# MultiDrop.net
KiCad netlist of a schematic drawn in EAGLE
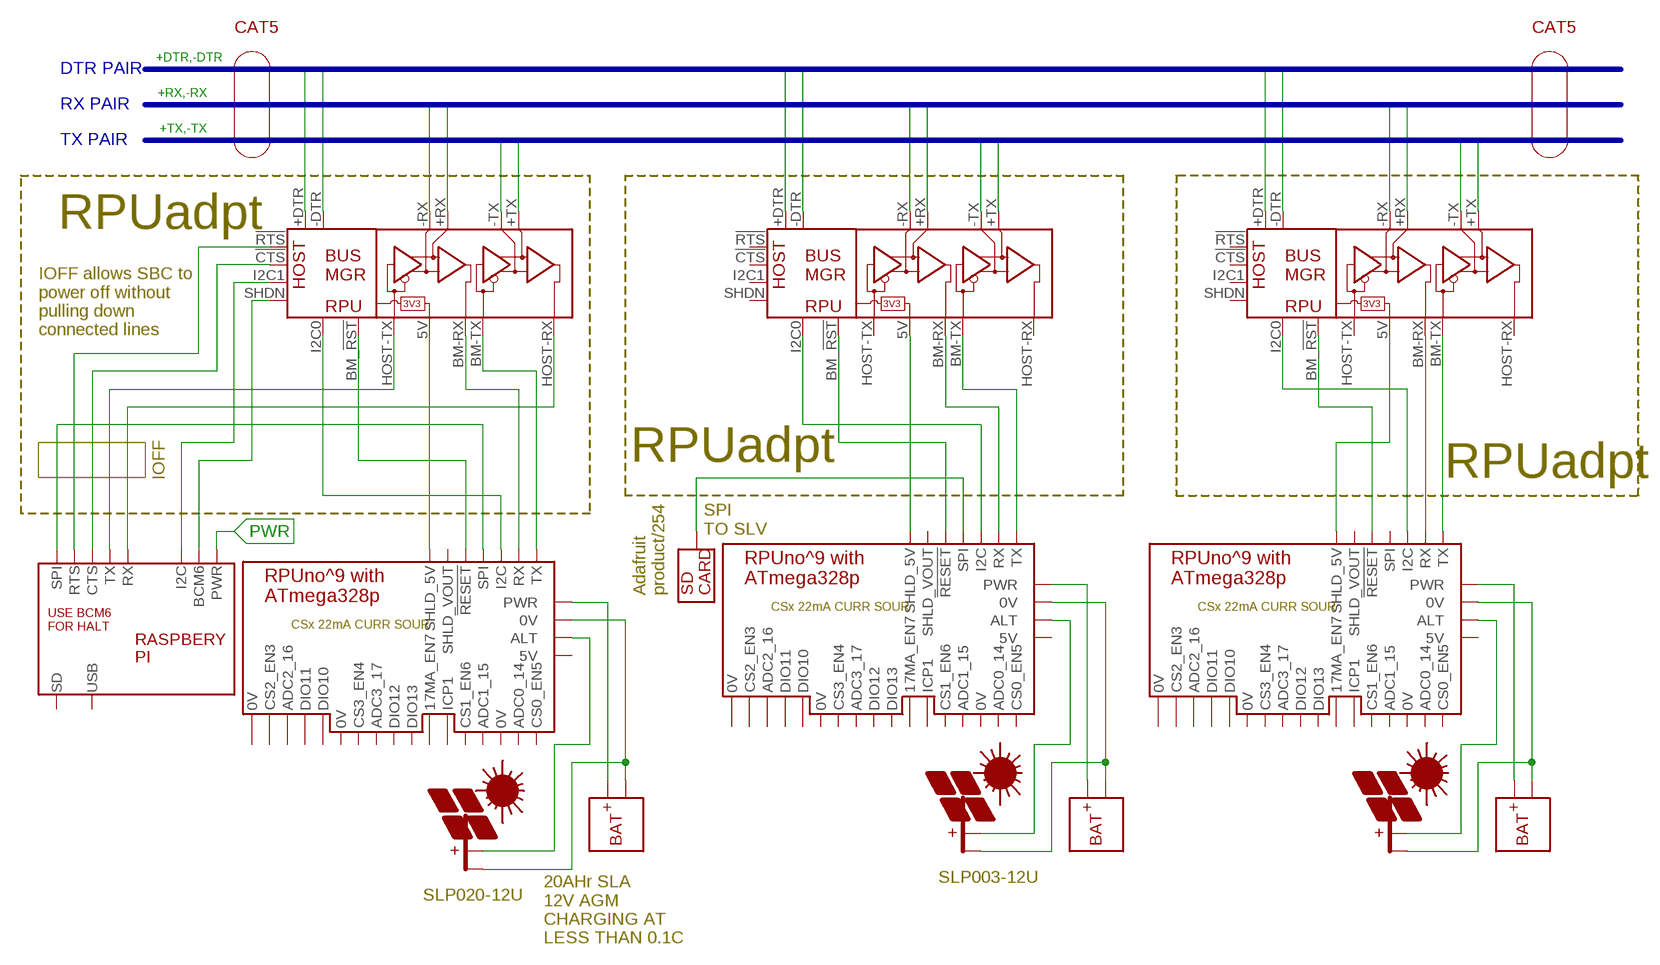
[diagram p0: schematic, sheet 1]

(export (version "E")
  (design (tool "Eeschema 10.0.6"))
  (components
    (comp (ref "BM1")
      (value "RPUNO")
      (footprint "eagle-import:NA-30")
      (libsource (lib "eagle-import") (part "RPUNO"))
    )
    (comp (ref "BM2")
      (value "RPUNO")
      (footprint "eagle-import:NA-30")
      (libsource (lib "eagle-import") (part "RPUNO"))
    )
    (comp (ref "BM3")
      (value "RPUNO")
      (footprint "eagle-import:NA-30")
      (libsource (lib "eagle-import") (part "RPUNO"))
    )
    (comp (ref "PV1")
      (value "PV")
      (footprint "eagle-import:NA-30")
      (libsource (lib "eagle-import") (part "PV"))
    )
    (comp (ref "PV2")
      (value "PV")
      (footprint "eagle-import:NA-30")
      (libsource (lib "eagle-import") (part "PV"))
    )
    (comp (ref "PV3")
      (value "PV")
      (footprint "eagle-import:NA-30")
      (libsource (lib "eagle-import") (part "PV"))
    )
    (comp (ref "SD1")
      (value "SD")
      (footprint "eagle-import:NA-30")
      (libsource (lib "eagle-import") (part "SD"))
    )
    (comp (ref "U$1")
      (value "BUS_MGR")
      (footprint "eagle-import:WITH_RPU_NAMES")
      (libsource (lib "eagle-import") (part "BUS_MGR"))
    )
    (comp (ref "U$2")
      (value "BUS_MGR")
      (footprint "eagle-import:WITH_RPU_NAMES")
      (libsource (lib "eagle-import") (part "BUS_MGR"))
    )
    (comp (ref "U$3")
      (value "BAT")
      (footprint "eagle-import:NA-30")
      (libsource (lib "eagle-import") (part "BAT"))
    )
    (comp (ref "U$4")
      (value "BUS_MGR")
      (footprint "eagle-import:WITH_RPU_NAMES")
      (libsource (lib "eagle-import") (part "BUS_MGR"))
    )
    (comp (ref "U$5")
      (value "BAT")
      (footprint "eagle-import:NA-30")
      (libsource (lib "eagle-import") (part "BAT"))
    )
    (comp (ref "U$7")
      (value "PI")
      (footprint "eagle-import:NA-30")
      (libsource (lib "eagle-import") (part "PI"))
    )
    (comp (ref "U$9")
      (value "BAT")
      (footprint "eagle-import:NA-30")
      (libsource (lib "eagle-import") (part "BAT"))
    )
  )
  (nets
    (net (code "10") (name "Net-(BM1-ALT)") (class "Default")
      (node (ref "BM1") (pin "20") (pinfunction "ALT_20") (pintype "bidirectional"))
      (node (ref "PV1") (pin "1") (pinfunction "+PV_1") (pintype "bidirectional"))
    )
    (net (code "11") (name "Net-(BM1-I2C)") (class "Default")
      (node (ref "BM1") (pin "3") (pinfunction "I2C_3") (pintype "bidirectional"))
      (node (ref "U$2") (pin "I2C0") (pinfunction "I2C0_I2C0") (pintype "bidirectional"))
    )
    (net (code "12") (name "Net-(BM1-PWR)") (class "Default")
      (node (ref "BM1") (pin "8") (pinfunction "PWR_8") (pintype "bidirectional"))
      (node (ref "U$3") (pin "1") (pinfunction "+BAT_1") (pintype "bidirectional"))
    )
    (net (code "13") (name "Net-(BM1-RX)") (class "Default")
      (node (ref "BM1") (pin "2") (pinfunction "RX_2") (pintype "bidirectional"))
      (node (ref "U$2") (pin "BM-RX") (pinfunction "BM_RX_BM-RX") (pintype "bidirectional"))
    )
    (net (code "14") (name "Net-(BM1-SHLD_5V)") (class "Default")
      (node (ref "BM1") (pin "6") (pinfunction "SHLD_5V_6") (pintype "bidirectional"))
      (node (ref "U$2") (pin "5V") (pinfunction "PWR_5V") (pintype "bidirectional"))
    )
    (net (code "15") (name "Net-(BM1-SPI)") (class "Default")
      (node (ref "BM1") (pin "4") (pinfunction "SPI_4") (pintype "bidirectional"))
      (node (ref "SD1") (pin "1") (pinfunction "PV_PWR_1") (pintype "bidirectional"))
    )
    (net (code "16") (name "Net-(BM1-TX)") (class "Default")
      (node (ref "BM1") (pin "1") (pinfunction "TX_1") (pintype "bidirectional"))
      (node (ref "U$2") (pin "BM-TX") (pinfunction "BM_TX_BM-TX") (pintype "bidirectional"))
    )
    (net (code "17") (name "Net-(BM1-~{RESET})") (class "Default")
      (node (ref "BM1") (pin "5") (pinfunction "~{RESET}_5") (pintype "bidirectional"))
      (node (ref "U$2") (pin "BM_!RST!") (pinfunction "BM-~{RST}_BM_!RST!") (pintype "bidirectional"))
    )
    (net (code "18") (name "Net-(BM2-ALT)") (class "Default")
      (node (ref "BM2") (pin "20") (pinfunction "ALT_20") (pintype "bidirectional"))
      (node (ref "PV2") (pin "1") (pinfunction "+PV_1") (pintype "bidirectional"))
    )
    (net (code "19") (name "Net-(BM2-I2C)") (class "Default")
      (node (ref "BM2") (pin "3") (pinfunction "I2C_3") (pintype "bidirectional"))
      (node (ref "U$1") (pin "I2C0") (pinfunction "I2C0_I2C0") (pintype "bidirectional"))
    )
    (net (code "20") (name "Net-(BM2-PWR)") (class "Default")
      (node (ref "BM2") (pin "8") (pinfunction "PWR_8") (pintype "bidirectional"))
      (node (ref "U$9") (pin "1") (pinfunction "+BAT_1") (pintype "bidirectional"))
    )
    (net (code "21") (name "Net-(BM2-RX)") (class "Default")
      (node (ref "BM2") (pin "2") (pinfunction "RX_2") (pintype "bidirectional"))
      (node (ref "U$1") (pin "BM-RX") (pinfunction "BM_RX_BM-RX") (pintype "bidirectional"))
    )
    (net (code "22") (name "Net-(BM2-SHLD_5V)") (class "Default")
      (node (ref "BM2") (pin "6") (pinfunction "SHLD_5V_6") (pintype "bidirectional"))
      (node (ref "U$1") (pin "5V") (pinfunction "PWR_5V") (pintype "bidirectional"))
    )
    (net (code "23") (name "Net-(BM2-SPI)") (class "Default")
      (node (ref "BM2") (pin "4") (pinfunction "SPI_4") (pintype "bidirectional"))
      (node (ref "U$7") (pin "10") (pinfunction "SPI_10") (pintype "bidirectional"))
    )
    (net (code "24") (name "Net-(BM2-TX)") (class "Default")
      (node (ref "BM2") (pin "1") (pinfunction "TX_1") (pintype "bidirectional"))
      (node (ref "U$1") (pin "BM-TX") (pinfunction "BM_TX_BM-TX") (pintype "bidirectional"))
    )
    (net (code "25") (name "Net-(BM2-~{RESET})") (class "Default")
      (node (ref "BM2") (pin "5") (pinfunction "~{RESET}_5") (pintype "bidirectional"))
      (node (ref "U$1") (pin "BM_!RST!") (pinfunction "BM-~{RST}_BM_!RST!") (pintype "bidirectional"))
    )
    (net (code "26") (name "Net-(BM3-ALT)") (class "Default")
      (node (ref "BM3") (pin "20") (pinfunction "ALT_20") (pintype "bidirectional"))
      (node (ref "PV3") (pin "1") (pinfunction "+PV_1") (pintype "bidirectional"))
    )
    (net (code "27") (name "Net-(BM3-I2C)") (class "Default")
      (node (ref "BM3") (pin "3") (pinfunction "I2C_3") (pintype "bidirectional"))
      (node (ref "U$4") (pin "I2C0") (pinfunction "I2C0_I2C0") (pintype "bidirectional"))
    )
    (net (code "28") (name "Net-(BM3-PWR)") (class "Default")
      (node (ref "BM3") (pin "8") (pinfunction "PWR_8") (pintype "bidirectional"))
      (node (ref "U$5") (pin "1") (pinfunction "+BAT_1") (pintype "bidirectional"))
    )
    (net (code "29") (name "Net-(BM3-RX)") (class "Default")
      (node (ref "BM3") (pin "2") (pinfunction "RX_2") (pintype "bidirectional"))
      (node (ref "U$4") (pin "BM-RX") (pinfunction "BM_RX_BM-RX") (pintype "bidirectional"))
    )
    (net (code "30") (name "Net-(BM3-SHLD_5V)") (class "Default")
      (node (ref "BM3") (pin "6") (pinfunction "SHLD_5V_6") (pintype "bidirectional"))
      (node (ref "U$4") (pin "5V") (pinfunction "PWR_5V") (pintype "bidirectional"))
    )
    (net (code "31") (name "Net-(BM3-TX)") (class "Default")
      (node (ref "BM3") (pin "1") (pinfunction "TX_1") (pintype "bidirectional"))
      (node (ref "U$4") (pin "BM-TX") (pinfunction "BM_TX_BM-TX") (pintype "bidirectional"))
    )
    (net (code "32") (name "Net-(BM3-~{RESET})") (class "Default")
      (node (ref "BM3") (pin "5") (pinfunction "~{RESET}_5") (pintype "bidirectional"))
      (node (ref "U$4") (pin "BM_!RST!") (pinfunction "BM-~{RST}_BM_!RST!") (pintype "bidirectional"))
    )
    (net (code "33") (name "Net-(PV1--PV)") (class "Default")
      (node (ref "BM1") (pin "9") (pinfunction "0V_9") (pintype "bidirectional"))
      (node (ref "PV1") (pin "2") (pinfunction "-PV_2") (pintype "bidirectional"))
      (node (ref "U$3") (pin "2") (pinfunction "-BAT_2") (pintype "bidirectional"))
    )
    (net (code "34") (name "Net-(PV2--PV)") (class "Default")
      (node (ref "BM2") (pin "9") (pinfunction "0V_9") (pintype "bidirectional"))
      (node (ref "PV2") (pin "2") (pinfunction "-PV_2") (pintype "bidirectional"))
      (node (ref "U$9") (pin "2") (pinfunction "-BAT_2") (pintype "bidirectional"))
    )
    (net (code "35") (name "Net-(PV3--PV)") (class "Default")
      (node (ref "BM3") (pin "9") (pinfunction "0V_9") (pintype "bidirectional"))
      (node (ref "PV3") (pin "2") (pinfunction "-PV_2") (pintype "bidirectional"))
      (node (ref "U$5") (pin "2") (pinfunction "-BAT_2") (pintype "bidirectional"))
    )
    (net (code "36") (name "Net-(U$1-HOST_RX)") (class "Default")
      (node (ref "U$1") (pin "HOST-RX") (pinfunction "HOST_RX_HOST-RX") (pintype "bidirectional"))
      (node (ref "U$7") (pin "3") (pinfunction "RX_3") (pintype "bidirectional"))
    )
    (net (code "37") (name "Net-(U$1-HOST_TX)") (class "Default")
      (node (ref "U$1") (pin "HOST-TX") (pinfunction "HOST_TX_HOST-TX") (pintype "bidirectional"))
      (node (ref "U$7") (pin "4") (pinfunction "TX_4") (pintype "bidirectional"))
    )
    (net (code "38") (name "Net-(U$1-~{CTS})") (class "Default")
      (node (ref "U$1") (pin "!CTS") (pinfunction "~{CTS}_!CTS") (pintype "bidirectional"))
      (node (ref "U$7") (pin "1") (pinfunction "CTS_1") (pintype "input"))
    )
    (net (code "39") (name "Net-(U$1-~{RTS})") (class "Default")
      (node (ref "U$1") (pin "!RTS") (pinfunction "~{RTS}_!RTS") (pintype "bidirectional"))
      (node (ref "U$7") (pin "2") (pinfunction "RTS_2") (pintype "input"))
    )
    (net (code "40") (name "Net-(U$7-BCM6)") (class "Default")
      (node (ref "U$1") (pin "SHDN") (pinfunction "SHDN_SHDN") (pintype "bidirectional"))
      (node (ref "U$7") (pin "7") (pinfunction "BCM6_7") (pintype "bidirectional"))
    )
    (net (code "41") (name "Net-(U$7-I2C)") (class "Default")
      (node (ref "U$1") (pin "I2C1") (pinfunction "I2C1_I2C1") (pintype "bidirectional"))
      (node (ref "U$7") (pin "8") (pinfunction "I2C_8") (pintype "bidirectional"))
    )
    (net (code "42") (name "PWR") (class "Default")
      (node (ref "U$7") (pin "12") (pinfunction "PWR_12") (pintype "bidirectional"))
    )
    (net (code "43") (name "unconnected-(BM1-0V-Pad26)") (class "Default")
      (node (ref "BM1") (pin "26") (pinfunction "0V_26") (pintype "bidirectional"))
    )
    (net (code "44") (name "unconnected-(BM1-0V-Pad27)") (class "Default")
      (node (ref "BM1") (pin "27") (pinfunction "0V_27") (pintype "bidirectional"))
    )
    (net (code "45") (name "unconnected-(BM1-0V-Pad28)") (class "Default")
      (node (ref "BM1") (pin "28") (pinfunction "0V_28") (pintype "bidirectional"))
    )
    (net (code "46") (name "unconnected-(BM1-5V-Pad19)") (class "Default")
      (node (ref "BM1") (pin "19") (pinfunction "5V_19") (pintype "bidirectional"))
    )
    (net (code "47") (name "unconnected-(BM1-17MA_EN7-Pad21)") (class "Default")
      (node (ref "BM1") (pin "21") (pinfunction "17MA_EN7_21") (pintype "bidirectional"))
    )
    (net (code "48") (name "unconnected-(BM1-ADC0_14-Pad11)") (class "Default")
      (node (ref "BM1") (pin "11") (pinfunction "ADC0_14_11") (pintype "bidirectional"))
    )
    (net (code "49") (name "unconnected-(BM1-ADC1_15-Pad10)") (class "Default")
      (node (ref "BM1") (pin "10") (pinfunction "ADC1_15_10") (pintype "bidirectional"))
    )
    (net (code "50") (name "unconnected-(BM1-ADC2_16-Pad13)") (class "Default")
      (node (ref "BM1") (pin "13") (pinfunction "ADC2_16_13") (pintype "bidirectional"))
    )
    (net (code "51") (name "unconnected-(BM1-ADC3_17-Pad16)") (class "Default")
      (node (ref "BM1") (pin "16") (pinfunction "ADC3_17_16") (pintype "bidirectional"))
    )
    (net (code "52") (name "unconnected-(BM1-CS0_EN5-Pad23)") (class "Default")
      (node (ref "BM1") (pin "23") (pinfunction "CS0_EN5_23") (pintype "bidirectional"))
    )
    (net (code "53") (name "unconnected-(BM1-CS1_EN6-Pad22)") (class "Default")
      (node (ref "BM1") (pin "22") (pinfunction "CS1_EN6_22") (pintype "bidirectional"))
    )
    (net (code "54") (name "unconnected-(BM1-CS2_EN3-Pad24)") (class "Default")
      (node (ref "BM1") (pin "24") (pinfunction "CS2_EN3_24") (pintype "bidirectional"))
    )
    (net (code "55") (name "unconnected-(BM1-CS3_EN4-Pad29)") (class "Default")
      (node (ref "BM1") (pin "29") (pinfunction "CS3_EN4_29") (pintype "bidirectional"))
    )
    (net (code "56") (name "unconnected-(BM1-DIO10-Pad15)") (class "Default")
      (node (ref "BM1") (pin "15") (pinfunction "DIO10_15") (pintype "bidirectional"))
    )
    (net (code "57") (name "unconnected-(BM1-DIO11-Pad14)") (class "Default")
      (node (ref "BM1") (pin "14") (pinfunction "DIO11_14") (pintype "bidirectional"))
    )
    (net (code "58") (name "unconnected-(BM1-DIO12-Pad17)") (class "Default")
      (node (ref "BM1") (pin "17") (pinfunction "DIO12_17") (pintype "bidirectional"))
    )
    (net (code "59") (name "unconnected-(BM1-DIO13-Pad18)") (class "Default")
      (node (ref "BM1") (pin "18") (pinfunction "DIO13_18") (pintype "bidirectional"))
    )
    (net (code "60") (name "unconnected-(BM1-ICP1-Pad12)") (class "Default")
      (node (ref "BM1") (pin "12") (pinfunction "ICP1_12") (pintype "bidirectional"))
    )
    (net (code "61") (name "unconnected-(BM1-SHLD_VOUT-Pad7)") (class "Default")
      (node (ref "BM1") (pin "7") (pinfunction "SHLD_VOUT_7") (pintype "bidirectional"))
    )
    (net (code "62") (name "unconnected-(BM2-0V-Pad26)") (class "Default")
      (node (ref "BM2") (pin "26") (pinfunction "0V_26") (pintype "bidirectional"))
    )
    (net (code "63") (name "unconnected-(BM2-0V-Pad27)") (class "Default")
      (node (ref "BM2") (pin "27") (pinfunction "0V_27") (pintype "bidirectional"))
    )
    (net (code "64") (name "unconnected-(BM2-0V-Pad28)") (class "Default")
      (node (ref "BM2") (pin "28") (pinfunction "0V_28") (pintype "bidirectional"))
    )
    (net (code "65") (name "unconnected-(BM2-5V-Pad19)") (class "Default")
      (node (ref "BM2") (pin "19") (pinfunction "5V_19") (pintype "bidirectional"))
    )
    (net (code "66") (name "unconnected-(BM2-17MA_EN7-Pad21)") (class "Default")
      (node (ref "BM2") (pin "21") (pinfunction "17MA_EN7_21") (pintype "bidirectional"))
    )
    (net (code "67") (name "unconnected-(BM2-ADC0_14-Pad11)") (class "Default")
      (node (ref "BM2") (pin "11") (pinfunction "ADC0_14_11") (pintype "bidirectional"))
    )
    (net (code "68") (name "unconnected-(BM2-ADC1_15-Pad10)") (class "Default")
      (node (ref "BM2") (pin "10") (pinfunction "ADC1_15_10") (pintype "bidirectional"))
    )
    (net (code "69") (name "unconnected-(BM2-ADC2_16-Pad13)") (class "Default")
      (node (ref "BM2") (pin "13") (pinfunction "ADC2_16_13") (pintype "bidirectional"))
    )
    (net (code "70") (name "unconnected-(BM2-ADC3_17-Pad16)") (class "Default")
      (node (ref "BM2") (pin "16") (pinfunction "ADC3_17_16") (pintype "bidirectional"))
    )
    (net (code "71") (name "unconnected-(BM2-CS0_EN5-Pad23)") (class "Default")
      (node (ref "BM2") (pin "23") (pinfunction "CS0_EN5_23") (pintype "bidirectional"))
    )
    (net (code "72") (name "unconnected-(BM2-CS1_EN6-Pad22)") (class "Default")
      (node (ref "BM2") (pin "22") (pinfunction "CS1_EN6_22") (pintype "bidirectional"))
    )
    (net (code "73") (name "unconnected-(BM2-CS2_EN3-Pad24)") (class "Default")
      (node (ref "BM2") (pin "24") (pinfunction "CS2_EN3_24") (pintype "bidirectional"))
    )
    (net (code "74") (name "unconnected-(BM2-CS3_EN4-Pad29)") (class "Default")
      (node (ref "BM2") (pin "29") (pinfunction "CS3_EN4_29") (pintype "bidirectional"))
    )
    (net (code "75") (name "unconnected-(BM2-DIO10-Pad15)") (class "Default")
      (node (ref "BM2") (pin "15") (pinfunction "DIO10_15") (pintype "bidirectional"))
    )
    (net (code "76") (name "unconnected-(BM2-DIO11-Pad14)") (class "Default")
      (node (ref "BM2") (pin "14") (pinfunction "DIO11_14") (pintype "bidirectional"))
    )
    (net (code "77") (name "unconnected-(BM2-DIO12-Pad17)") (class "Default")
      (node (ref "BM2") (pin "17") (pinfunction "DIO12_17") (pintype "bidirectional"))
    )
    (net (code "78") (name "unconnected-(BM2-DIO13-Pad18)") (class "Default")
      (node (ref "BM2") (pin "18") (pinfunction "DIO13_18") (pintype "bidirectional"))
    )
    (net (code "79") (name "unconnected-(BM2-ICP1-Pad12)") (class "Default")
      (node (ref "BM2") (pin "12") (pinfunction "ICP1_12") (pintype "bidirectional"))
    )
    (net (code "80") (name "unconnected-(BM2-SHLD_VOUT-Pad7)") (class "Default")
      (node (ref "BM2") (pin "7") (pinfunction "SHLD_VOUT_7") (pintype "bidirectional"))
    )
    (net (code "81") (name "unconnected-(BM3-0V-Pad26)") (class "Default")
      (node (ref "BM3") (pin "26") (pinfunction "0V_26") (pintype "bidirectional"))
    )
    (net (code "82") (name "unconnected-(BM3-0V-Pad27)") (class "Default")
      (node (ref "BM3") (pin "27") (pinfunction "0V_27") (pintype "bidirectional"))
    )
    (net (code "83") (name "unconnected-(BM3-0V-Pad28)") (class "Default")
      (node (ref "BM3") (pin "28") (pinfunction "0V_28") (pintype "bidirectional"))
    )
    (net (code "84") (name "unconnected-(BM3-5V-Pad19)") (class "Default")
      (node (ref "BM3") (pin "19") (pinfunction "5V_19") (pintype "bidirectional"))
    )
    (net (code "85") (name "unconnected-(BM3-17MA_EN7-Pad21)") (class "Default")
      (node (ref "BM3") (pin "21") (pinfunction "17MA_EN7_21") (pintype "bidirectional"))
    )
    (net (code "86") (name "unconnected-(BM3-ADC0_14-Pad11)") (class "Default")
      (node (ref "BM3") (pin "11") (pinfunction "ADC0_14_11") (pintype "bidirectional"))
    )
    (net (code "87") (name "unconnected-(BM3-ADC1_15-Pad10)") (class "Default")
      (node (ref "BM3") (pin "10") (pinfunction "ADC1_15_10") (pintype "bidirectional"))
    )
    (net (code "88") (name "unconnected-(BM3-ADC2_16-Pad13)") (class "Default")
      (node (ref "BM3") (pin "13") (pinfunction "ADC2_16_13") (pintype "bidirectional"))
    )
    (net (code "89") (name "unconnected-(BM3-ADC3_17-Pad16)") (class "Default")
      (node (ref "BM3") (pin "16") (pinfunction "ADC3_17_16") (pintype "bidirectional"))
    )
    (net (code "90") (name "unconnected-(BM3-CS0_EN5-Pad23)") (class "Default")
      (node (ref "BM3") (pin "23") (pinfunction "CS0_EN5_23") (pintype "bidirectional"))
    )
    (net (code "91") (name "unconnected-(BM3-CS1_EN6-Pad22)") (class "Default")
      (node (ref "BM3") (pin "22") (pinfunction "CS1_EN6_22") (pintype "bidirectional"))
    )
    (net (code "92") (name "unconnected-(BM3-CS2_EN3-Pad24)") (class "Default")
      (node (ref "BM3") (pin "24") (pinfunction "CS2_EN3_24") (pintype "bidirectional"))
    )
    (net (code "93") (name "unconnected-(BM3-CS3_EN4-Pad29)") (class "Default")
      (node (ref "BM3") (pin "29") (pinfunction "CS3_EN4_29") (pintype "bidirectional"))
    )
    (net (code "94") (name "unconnected-(BM3-DIO10-Pad15)") (class "Default")
      (node (ref "BM3") (pin "15") (pinfunction "DIO10_15") (pintype "bidirectional"))
    )
    (net (code "95") (name "unconnected-(BM3-DIO11-Pad14)") (class "Default")
      (node (ref "BM3") (pin "14") (pinfunction "DIO11_14") (pintype "bidirectional"))
    )
    (net (code "96") (name "unconnected-(BM3-DIO12-Pad17)") (class "Default")
      (node (ref "BM3") (pin "17") (pinfunction "DIO12_17") (pintype "bidirectional"))
    )
    (net (code "97") (name "unconnected-(BM3-DIO13-Pad18)") (class "Default")
      (node (ref "BM3") (pin "18") (pinfunction "DIO13_18") (pintype "bidirectional"))
    )
    (net (code "98") (name "unconnected-(BM3-ICP1-Pad12)") (class "Default")
      (node (ref "BM3") (pin "12") (pinfunction "ICP1_12") (pintype "bidirectional"))
    )
    (net (code "99") (name "unconnected-(BM3-SHLD_VOUT-Pad7)") (class "Default")
      (node (ref "BM3") (pin "7") (pinfunction "SHLD_VOUT_7") (pintype "bidirectional"))
    )
    (net (code "100") (name "unconnected-(BM3-SPI-Pad4)") (class "Default")
      (node (ref "BM3") (pin "4") (pinfunction "SPI_4") (pintype "bidirectional"))
    )
    (net (code "101") (name "unconnected-(U$1-Pad+DTR)") (class "Default")
      (node (ref "U$1") (pin "+DTR") (pinfunction "+DTR_+DTR") (pintype "bidirectional"))
    )
    (net (code "102") (name "unconnected-(U$1-Pad+RX)") (class "Default")
      (node (ref "U$1") (pin "+RX") (pinfunction "+RX_+RX") (pintype "bidirectional"))
    )
    (net (code "103") (name "unconnected-(U$1-Pad+TX)") (class "Default")
      (node (ref "U$1") (pin "+TX") (pinfunction "+TX_+TX") (pintype "bidirectional"))
    )
    (net (code "104") (name "unconnected-(U$1-Pad-DTR)") (class "Default")
      (node (ref "U$1") (pin "-DTR") (pinfunction "-DTR_-DTR") (pintype "bidirectional"))
    )
    (net (code "105") (name "unconnected-(U$1-Pad-RX)") (class "Default")
      (node (ref "U$1") (pin "-RX") (pinfunction "-RX_-RX") (pintype "bidirectional"))
    )
    (net (code "106") (name "unconnected-(U$1-Pad-TX)") (class "Default")
      (node (ref "U$1") (pin "-TX") (pinfunction "-TX_-TX") (pintype "bidirectional"))
    )
    (net (code "107") (name "unconnected-(U$2-HOST_RX-PadHOST-RX)") (class "Default")
      (node (ref "U$2") (pin "HOST-RX") (pinfunction "HOST_RX_HOST-RX") (pintype "bidirectional"))
    )
    (net (code "108") (name "unconnected-(U$2-HOST_TX-PadHOST-TX)") (class "Default")
      (node (ref "U$2") (pin "HOST-TX") (pinfunction "HOST_TX_HOST-TX") (pintype "bidirectional"))
    )
    (net (code "109") (name "unconnected-(U$2-Pad+DTR)") (class "Default")
      (node (ref "U$2") (pin "+DTR") (pinfunction "+DTR_+DTR") (pintype "bidirectional"))
    )
    (net (code "110") (name "unconnected-(U$2-Pad+RX)") (class "Default")
      (node (ref "U$2") (pin "+RX") (pinfunction "+RX_+RX") (pintype "bidirectional"))
    )
    (net (code "111") (name "unconnected-(U$2-Pad+TX)") (class "Default")
      (node (ref "U$2") (pin "+TX") (pinfunction "+TX_+TX") (pintype "bidirectional"))
    )
    (net (code "112") (name "unconnected-(U$2-Pad-DTR)") (class "Default")
      (node (ref "U$2") (pin "-DTR") (pinfunction "-DTR_-DTR") (pintype "bidirectional"))
    )
    (net (code "113") (name "unconnected-(U$2-Pad-RX)") (class "Default")
      (node (ref "U$2") (pin "-RX") (pinfunction "-RX_-RX") (pintype "bidirectional"))
    )
    (net (code "114") (name "unconnected-(U$2-Pad-TX)") (class "Default")
      (node (ref "U$2") (pin "-TX") (pinfunction "-TX_-TX") (pintype "bidirectional"))
    )
    (net (code "115") (name "unconnected-(U$2-PadI2C1)") (class "Default")
      (node (ref "U$2") (pin "I2C1") (pinfunction "I2C1_I2C1") (pintype "bidirectional"))
    )
    (net (code "116") (name "unconnected-(U$2-PadSHDN)") (class "Default")
      (node (ref "U$2") (pin "SHDN") (pinfunction "SHDN_SHDN") (pintype "bidirectional"))
    )
    (net (code "117") (name "unconnected-(U$2-~{CTS}-Pad!CTS)") (class "Default")
      (node (ref "U$2") (pin "!CTS") (pinfunction "~{CTS}_!CTS") (pintype "bidirectional"))
    )
    (net (code "118") (name "unconnected-(U$2-~{RTS}-Pad!RTS)") (class "Default")
      (node (ref "U$2") (pin "!RTS") (pinfunction "~{RTS}_!RTS") (pintype "bidirectional"))
    )
    (net (code "119") (name "unconnected-(U$4-HOST_RX-PadHOST-RX)") (class "Default")
      (node (ref "U$4") (pin "HOST-RX") (pinfunction "HOST_RX_HOST-RX") (pintype "bidirectional"))
    )
    (net (code "120") (name "unconnected-(U$4-HOST_TX-PadHOST-TX)") (class "Default")
      (node (ref "U$4") (pin "HOST-TX") (pinfunction "HOST_TX_HOST-TX") (pintype "bidirectional"))
    )
    (net (code "121") (name "unconnected-(U$4-Pad+DTR)") (class "Default")
      (node (ref "U$4") (pin "+DTR") (pinfunction "+DTR_+DTR") (pintype "bidirectional"))
    )
    (net (code "122") (name "unconnected-(U$4-Pad+RX)") (class "Default")
      (node (ref "U$4") (pin "+RX") (pinfunction "+RX_+RX") (pintype "bidirectional"))
    )
    (net (code "123") (name "unconnected-(U$4-Pad+TX)") (class "Default")
      (node (ref "U$4") (pin "+TX") (pinfunction "+TX_+TX") (pintype "bidirectional"))
    )
    (net (code "124") (name "unconnected-(U$4-Pad-DTR)") (class "Default")
      (node (ref "U$4") (pin "-DTR") (pinfunction "-DTR_-DTR") (pintype "bidirectional"))
    )
    (net (code "125") (name "unconnected-(U$4-Pad-RX)") (class "Default")
      (node (ref "U$4") (pin "-RX") (pinfunction "-RX_-RX") (pintype "bidirectional"))
    )
    (net (code "126") (name "unconnected-(U$4-Pad-TX)") (class "Default")
      (node (ref "U$4") (pin "-TX") (pinfunction "-TX_-TX") (pintype "bidirectional"))
    )
    (net (code "127") (name "unconnected-(U$4-PadI2C1)") (class "Default")
      (node (ref "U$4") (pin "I2C1") (pinfunction "I2C1_I2C1") (pintype "bidirectional"))
    )
    (net (code "128") (name "unconnected-(U$4-PadSHDN)") (class "Default")
      (node (ref "U$4") (pin "SHDN") (pinfunction "SHDN_SHDN") (pintype "bidirectional"))
    )
    (net (code "129") (name "unconnected-(U$4-~{CTS}-Pad!CTS)") (class "Default")
      (node (ref "U$4") (pin "!CTS") (pinfunction "~{CTS}_!CTS") (pintype "bidirectional"))
    )
    (net (code "130") (name "unconnected-(U$4-~{RTS}-Pad!RTS)") (class "Default")
      (node (ref "U$4") (pin "!RTS") (pinfunction "~{RTS}_!RTS") (pintype "bidirectional"))
    )
    (net (code "131") (name "unconnected-(U$7-SD-Pad9)") (class "Default")
      (node (ref "U$7") (pin "9") (pinfunction "SD_9") (pintype "input"))
    )
    (net (code "132") (name "unconnected-(U$7-USB-Pad11)") (class "Default")
      (node (ref "U$7") (pin "11") (pinfunction "USB_11") (pintype "input"))
    )
  )
)
